# 07_RFID_LCD.net
KiCad netlist of a schematic drawn in Altium Designer
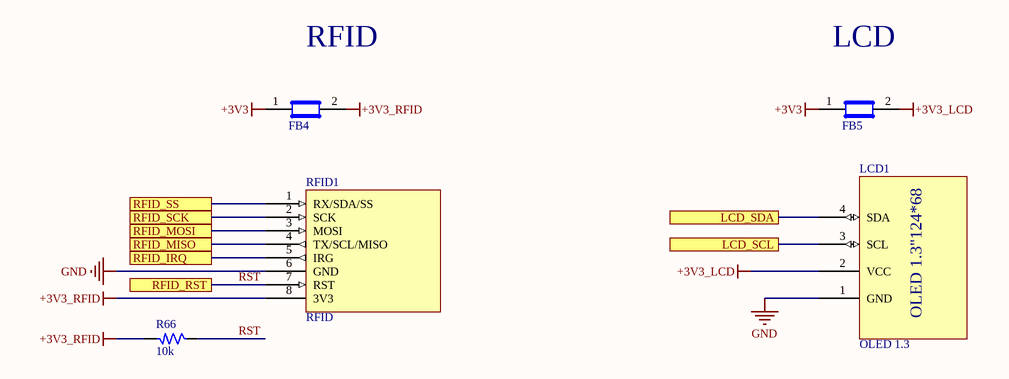
[diagram p0: [07] RFID_LCD.SchDoc]

(export (version "E")
  (design (tool "Eeschema 10.0.6"))
  (components
    (comp (ref "FB4")
      (value "BLM21PG600SN1D")
      (footprint "R0805")
      (description "Ferrite Bead")
      (libsource (lib "GPS_Traking_V1_1") (part "Ferrite Bead"))
    )
    (comp (ref "FB5")
      (value "BLM21PG600SN1D")
      (footprint "R0805")
      (description "Ferrite Bead")
      (libsource (lib "GPS_Traking_V1_1") (part "Ferrite Bead"))
    )
    (comp (ref "LCD1")
      (value "OLED 1.3")
      (footprint "My Library:OLED 1.3")
      (libsource (lib "My Library") (part "OLED 1.3"))
    )
    (comp (ref "R66")
      (value "10k")
      (footprint "R0805")
      (description "Resistor SMD")
      (libsource (lib "GPS_Traking_V1_1") (part "RM"))
    )
    (comp (ref "RFID1")
      (value "RFID")
      (footprint "RFID RC522")
      (libsource (lib "My Library") (part "RFID RC522"))
    )
  )
  (nets
    (net (code "1") (name "+3V3") (class "Default")
      (node (ref "FB4") (pin "1") (pinfunction "1_1") (pintype "passive"))
      (node (ref "FB5") (pin "1") (pinfunction "1_1") (pintype "passive"))
    )
    (net (code "2") (name "+3V3_LCD") (class "Default")
      (node (ref "FB5") (pin "2") (pinfunction "2_2") (pintype "passive"))
      (node (ref "LCD1") (pin "2") (pinfunction "VCC_2") (pintype "power_in"))
    )
    (net (code "3") (name "+3V3_RFID") (class "Default")
      (node (ref "FB4") (pin "2") (pinfunction "2_2") (pintype "passive"))
      (node (ref "R66") (pin "2") (pinfunction "2_2") (pintype "passive"))
      (node (ref "RFID1") (pin "8") (pinfunction "3V3_8") (pintype "power_in"))
    )
    (net (code "4") (name "/LCD_SCL") (class "Default")
      (node (ref "LCD1") (pin "3") (pinfunction "SCL_3") (pintype "bidirectional"))
    )
    (net (code "5") (name "/LCD_SDA") (class "Default")
      (node (ref "LCD1") (pin "4") (pinfunction "SDA_4") (pintype "bidirectional"))
    )
    (net (code "6") (name "/RFID_IRQ") (class "Default")
      (node (ref "RFID1") (pin "5") (pinfunction "IRG_5") (pintype "output"))
    )
    (net (code "7") (name "/RFID_MISO") (class "Default")
      (node (ref "RFID1") (pin "4") (pinfunction "TX/SCL/MISO_4") (pintype "output"))
    )
    (net (code "8") (name "/RFID_MOSI") (class "Default")
      (node (ref "RFID1") (pin "3") (pinfunction "MOSI_3") (pintype "input"))
    )
    (net (code "9") (name "/RFID_SCK") (class "Default")
      (node (ref "RFID1") (pin "2") (pinfunction "SCK_2") (pintype "input"))
    )
    (net (code "10") (name "/RFID_SS") (class "Default")
      (node (ref "RFID1") (pin "1") (pinfunction "RX/SDA/SS_1") (pintype "input"))
    )
    (net (code "11") (name "/RST") (class "Default")
      (node (ref "R66") (pin "1") (pinfunction "1_1") (pintype "passive"))
      (node (ref "RFID1") (pin "7") (pinfunction "RST_7") (pintype "input"))
    )
    (net (code "12") (name "GND") (class "Default")
      (node (ref "LCD1") (pin "1") (pinfunction "GND_1") (pintype "power_in"))
      (node (ref "RFID1") (pin "6") (pinfunction "GND_6") (pintype "power_in"))
    )
  )
)
